# Solenoid_8.net
KiCad netlist of a schematic drawn in EAGLE
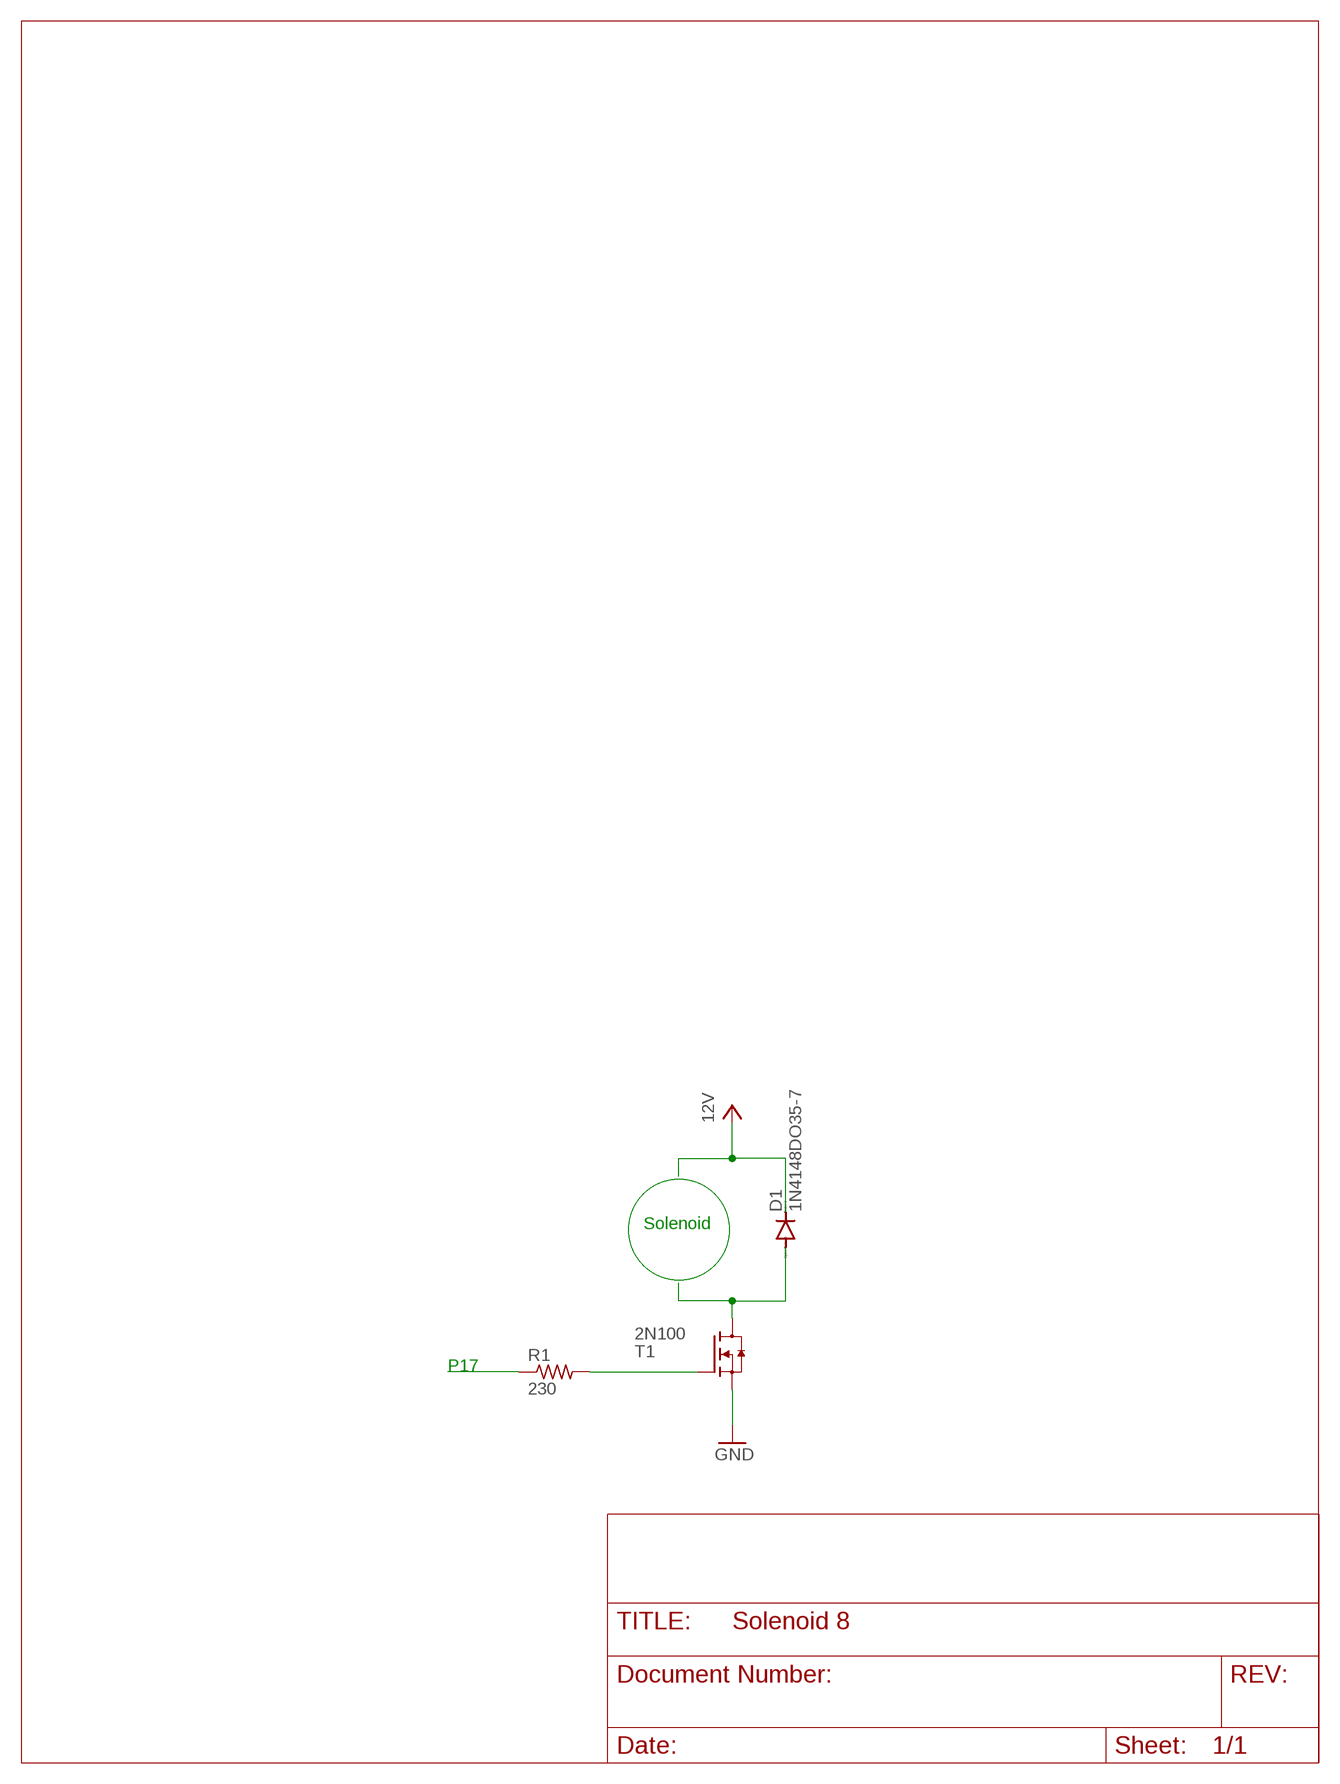
[diagram p0: schematic, sheet 1]

(export (version "E")
  (design (tool "Eeschema 10.0.6"))
  (components
    (comp (ref "D1")
      (value "1N4148DO35-7")
      (footprint "eagle-import:DO35-7")
      (libsource (lib "eagle-import") (part "1N4148DO35-7"))
    )
    (comp (ref "R1")
      (value "230")
      (footprint "eagle-import:0204_7")
      (libsource (lib "eagle-import") (part "R-US_0204/7"))
    )
    (comp (ref "T1")
      (value "2N100")
      (footprint "eagle-import:PG-TO263-7-3")
      (libsource (lib "eagle-import") (part "IPB180N06S4-H1"))
    )
  )
  (nets
    (net (code "1") (name "12V") (class "Default")
      (node (ref "D1") (pin "C") (pinfunction "C_C") (pintype "passive"))
    )
    (net (code "2") (name "GND") (class "Default")
      (node (ref "T1") (pin "2") (pinfunction "S_2") (pintype "passive"))
      (node (ref "T1") (pin "3") (pinfunction "S_3") (pintype "passive"))
      (node (ref "T1") (pin "5") (pinfunction "S_5") (pintype "passive"))
      (node (ref "T1") (pin "6") (pinfunction "S_6") (pintype "passive"))
      (node (ref "T1") (pin "7") (pinfunction "S_7") (pintype "passive"))
    )
    (net (code "3") (name "Net-(T1-D)") (class "Default")
      (node (ref "D1") (pin "A") (pinfunction "A_A") (pintype "passive"))
      (node (ref "T1") (pin "8") (pinfunction "D_8") (pintype "passive"))
    )
    (net (code "4") (name "Net-(T1-G)") (class "Default")
      (node (ref "R1") (pin "2") (pinfunction "2_2") (pintype "passive"))
      (node (ref "T1") (pin "1") (pinfunction "G_1") (pintype "passive"))
    )
    (net (code "5") (name "unconnected-(R1-Pad1)") (class "Default")
      (node (ref "R1") (pin "1") (pinfunction "1_1") (pintype "passive"))
    )
  )
)
